# volt_mon.net
KiCad netlist of a schematic drawn in Altium Designer
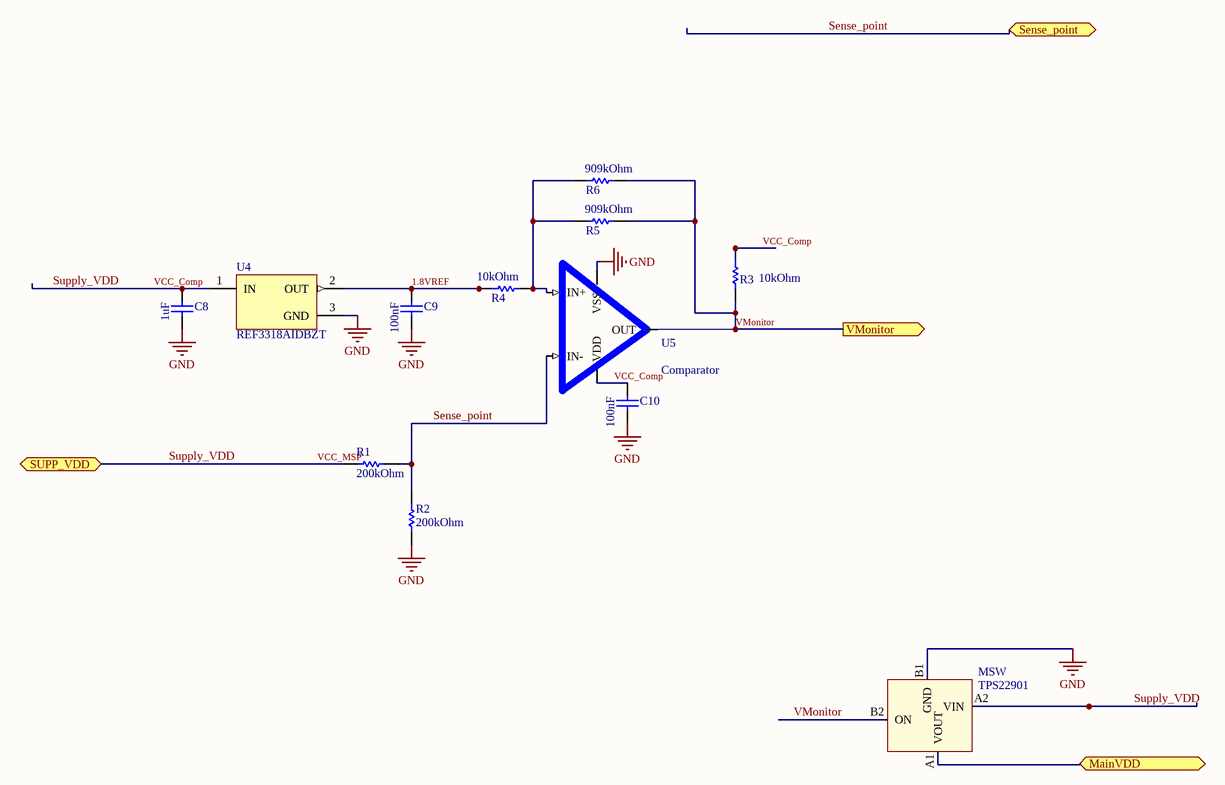
[diagram p0: volt_mon.SchDoc]

(export (version "E")
  (design (tool "Eeschema 10.0.6"))
  (components
    (comp (ref "C8")
      (value "1uF")
      (footprint "CAPC0402(1005)60_N")
      (description "CAP 1uF 4V ±10% 0402 (1005 Metric) Thickness 0.6mm SMD")
      (fields (field (name "TOLERANCE") "±10%") (field (name "Comment") "CAP 1uF 4V 0402(1005)"))
      (libsource (lib "Altium Content Vault") (part "CMP-1034-02111-1"))
    )
    (comp (ref "C9")
      (value "100nF")
      (footprint "CAPC0402(1005)60_N")
      (description "CAP 1uF 4V ±10% 0402 (1005 Metric) Thickness 0.6mm SMD")
      (fields (field (name "TOLERANCE") "±10%") (field (name "Comment") "CAP 1uF 4V 0402(1005)"))
      (libsource (lib "Altium Content Vault") (part "CMP-1034-02111-1"))
    )
    (comp (ref "C10")
      (value "100nF")
      (footprint "CAPC0402(1005)60_N")
      (description "CAP 1uF 4V ±10% 0402 (1005 Metric) Thickness 0.6mm SMD")
      (fields (field (name "TOLERANCE") "±10%") (field (name "Comment") "CAP 1uF 4V 0402(1005)"))
      (libsource (lib "Altium Content Vault") (part "CMP-1034-02111-1"))
    )
    (comp (ref "MSW")
      (value "TPS22901")
      (footprint "BGA4C40P2X2_76X76X50")
      (libsource (lib "Basic_components_hrishi") (part "TPS22901"))
    )
    (comp (ref "R1")
      (value "200kOhm")
      (footprint "RESC0805(2012)_M")
      (description "3R3 0.125W 5% 0805 (2012 Metric)  SMD")
      (fields (field (name "TOLERANCE") "5 %") (field (name "POWER") "0.125 W"))
      (libsource (lib "Altium Content Vault") (part "CMP-1013-00014-1"))
    )
    (comp (ref "R2")
      (value "200kOhm")
      (footprint "RESC0805(2012)_M")
      (description "3R3 0.125W 5% 0805 (2012 Metric)  SMD")
      (fields (field (name "TOLERANCE") "5 %") (field (name "POWER") "0.125 W"))
      (libsource (lib "Altium Content Vault") (part "CMP-1013-00014-1"))
    )
    (comp (ref "R3")
      (value "10kOhm")
      (footprint "RESC0805(2012)_M")
      (description "3R3 0.125W 5% 0805 (2012 Metric)  SMD")
      (fields (field (name "TOLERANCE") "5 %") (field (name "POWER") "0.125 W"))
      (libsource (lib "Altium Content Vault") (part "CMP-1013-00014-1"))
    )
    (comp (ref "R4")
      (value "10kOhm")
      (footprint "RESC0805(2012)_M")
      (description "3R3 0.125W 5% 0805 (2012 Metric)  SMD")
      (fields (field (name "TOLERANCE") "5 %") (field (name "POWER") "0.125 W"))
      (libsource (lib "Altium Content Vault") (part "CMP-1013-00014-1"))
    )
    (comp (ref "R5")
      (value "909kOhm")
      (footprint "RESC0805(2012)_M")
      (description "3R3 0.125W 5% 0805 (2012 Metric)  SMD")
      (fields (field (name "TOLERANCE") "5 %") (field (name "POWER") "0.125 W"))
      (libsource (lib "Altium Content Vault") (part "CMP-1013-00014-1"))
    )
    (comp (ref "R6")
      (value "909kOhm")
      (footprint "RESC0805(2012)_M")
      (description "3R3 0.125W 5% 0805 (2012 Metric)  SMD")
      (fields (field (name "TOLERANCE") "5 %") (field (name "POWER") "0.125 W"))
      (libsource (lib "Altium Content Vault") (part "CMP-1013-00014-1"))
    )
    (comp (ref "U4")
      (value "REF3318AIDBZT")
      (footprint "TI-DBZ3_N")
      (fields (field (name "MANUFACTURER") "Texas Instruments"))
      (libsource (lib "Altium Content Vault") (part "CMP-0367-00129-1"))
    )
    (comp (ref "U5")
      (value "Comparator")
      (footprint "SOT95P270X145-5N")
      (libsource (lib "Basic_components_hrishi") (part "Comparator"))
    )
  )
  (nets
    (net (code "1") (name "/1.8VREF") (class "Default")
      (node (ref "C9") (pin "2") (pinfunction "2_2") (pintype "passive"))
      (node (ref "R4") (pin "2") (pinfunction "2_2") (pintype "passive"))
      (node (ref "U4") (pin "2") (pinfunction "OUT_2") (pintype "output"))
    )
    (net (code "2") (name "/MainVDD") (class "Default")
      (node (ref "MSW") (pin "A1") (pinfunction "VOUT_A1") (pintype "passive"))
    )
    (net (code "3") (name "/Sense_point") (class "Default")
      (node (ref "R1") (pin "2") (pinfunction "2_2") (pintype "passive"))
      (node (ref "R2") (pin "2") (pinfunction "2_2") (pintype "passive"))
      (node (ref "U5") (pin "input-") (pinfunction "IN-_input-") (pintype "input"))
    )
    (net (code "4") (name "/Supply_VDD") (class "Default")
      (node (ref "C10") (pin "2") (pinfunction "2_2") (pintype "passive"))
      (node (ref "C8") (pin "2") (pinfunction "2_2") (pintype "passive"))
      (node (ref "MSW") (pin "A2") (pinfunction "VIN_A2") (pintype "passive"))
      (node (ref "R1") (pin "1") (pinfunction "1_1") (pintype "passive"))
      (node (ref "R3") (pin "2") (pinfunction "2_2") (pintype "passive"))
      (node (ref "U4") (pin "1") (pinfunction "IN_1") (pintype "power_in"))
      (node (ref "U5") (pin "VDD") (pinfunction "VDD_VDD") (pintype "power_in"))
    )
    (net (code "5") (name "/VMonitor") (class "Default")
      (node (ref "MSW") (pin "B2") (pinfunction "ON_B2") (pintype "passive"))
      (node (ref "R3") (pin "1") (pinfunction "1_1") (pintype "passive"))
      (node (ref "R5") (pin "1") (pinfunction "1_1") (pintype "passive"))
      (node (ref "R6") (pin "1") (pinfunction "1_1") (pintype "passive"))
      (node (ref "U5") (pin "OUT") (pinfunction "OUT_OUT") (pintype "open_collector"))
    )
    (net (code "6") (name "GND") (class "Default")
      (node (ref "C10") (pin "1") (pinfunction "1_1") (pintype "passive"))
      (node (ref "C8") (pin "1") (pinfunction "1_1") (pintype "passive"))
      (node (ref "C9") (pin "1") (pinfunction "1_1") (pintype "passive"))
      (node (ref "MSW") (pin "B1") (pinfunction "GND_B1") (pintype "passive"))
      (node (ref "R2") (pin "1") (pinfunction "1_1") (pintype "passive"))
      (node (ref "U4") (pin "3") (pinfunction "GND_3") (pintype "power_in"))
      (node (ref "U5") (pin "GND") (pinfunction "VSS_GND") (pintype "power_in"))
    )
    (net (code "7") (name "Net-(U5-IN+)") (class "Default")
      (node (ref "R4") (pin "1") (pinfunction "1_1") (pintype "passive"))
      (node (ref "R5") (pin "2") (pinfunction "2_2") (pintype "passive"))
      (node (ref "R6") (pin "2") (pinfunction "2_2") (pintype "passive"))
      (node (ref "U5") (pin "input+") (pinfunction "IN+_input+") (pintype "input"))
    )
  )
)
